# MCP1726_PINOUT.net
KiCad netlist of a schematic drawn in Altium Designer
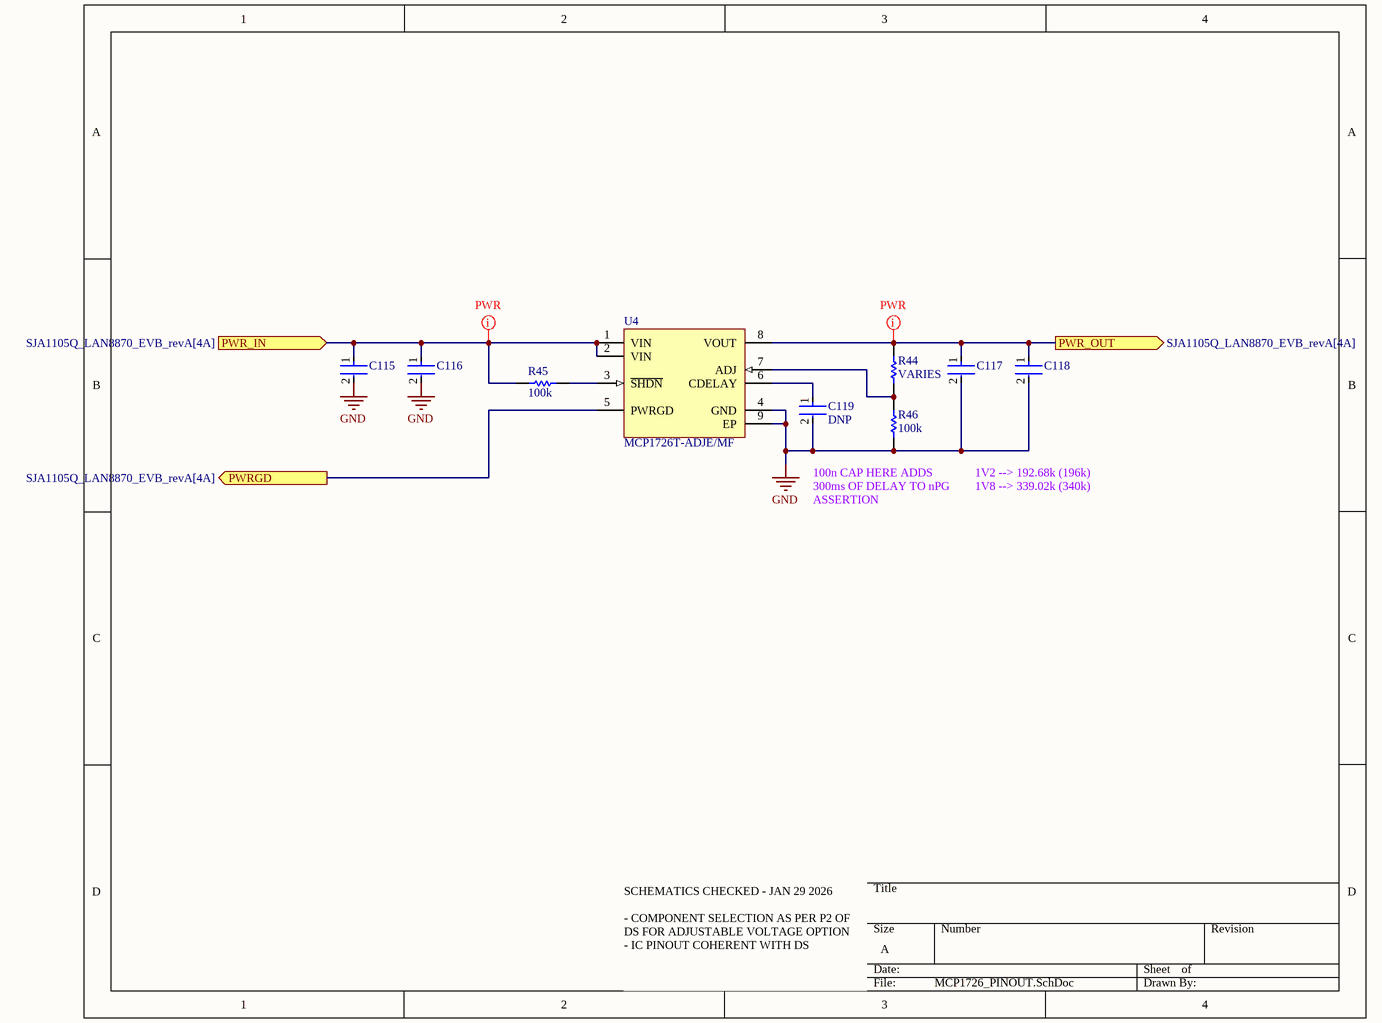
[diagram p0: MCP1726_PINOUT.SchDoc]

(export (version "E")
  (design (tool "Eeschema 10.0.6"))
  (components
    (comp (ref "C115")
      (value "C0805C475J4RACAUTO")
      (footprint "FP-C0805C475J4RACAUTO-MFG")
      (description "C0805C475J4RACAUTO Cap Ceramic 4.7uF 16V X7R 5% Pad SMD 0805 125C Automotive T/R")
      (fields (field (name "TOLERANCE") "5%"))
      (libsource (lib "Altium Content Vault") (part "b4654b650e69147ec39a6b967a45e02"))
    )
    (comp (ref "C116")
      (value "DNP")
      (footprint "FP-C0805C475J4RACAUTO-MFG")
      (description "C0805C475J4RACAUTO Cap Ceramic 4.7uF 16V X7R 5% Pad SMD 0805 125C Automotive T/R")
      (fields (field (name "TOLERANCE") "5%"))
      (libsource (lib "Altium Content Vault") (part "b4654b650e69147ec39a6b967a45e02"))
    )
    (comp (ref "C117")
      (value "HMK325B7105KN-T")
      (footprint "FP-1210-L_3_2_0_3-W_2_5_0-IPC_B")
      (description "None")
      (fields (field (name "TOLERANCE") "10%") (field (name "VOLTAGE") "100V"))
      (libsource (lib "Altium Content Vault") (part "02cd4be3c70576c341d710602a673aa"))
    )
    (comp (ref "C118")
      (value "DNP")
      (footprint "FP-1210-L_3_2_0_3-W_2_5_0-IPC_B")
      (description "None")
      (fields (field (name "TOLERANCE") "10%") (field (name "VOLTAGE") "100V"))
      (libsource (lib "Altium Content Vault") (part "02cd4be3c70576c341d710602a673aa"))
    )
    (comp (ref "C119")
      (value "DNP")
      (footprint "FP-0402-L_1_0_0_05-W_0_5-IPC_A")
      (description "LARGE PADS, 0402 CAP, CHANGE COMMENT TO MATCH REAL P/N")
      (libsource (lib "Space Concordia") (part "b4654b650e69147ec39a6b967a45e02"))
    )
    (comp (ref "R44")
      (value "VARIES")
      (footprint "R0603B")
      (description "Resistor")
      (libsource (lib "Space Concordia") (part "Resistor"))
    )
    (comp (ref "R45")
      (value "100k")
      (footprint "R0603B")
      (description "Resistor")
      (libsource (lib "Space Concordia") (part "Resistor"))
    )
    (comp (ref "R46")
      (value "100k")
      (footprint "R0603B")
      (description "Resistor")
      (libsource (lib "Space Concordia") (part "Resistor"))
    )
    (comp (ref "U4")
      (value "MCP1726T-ADJE/MF")
      (footprint "DFN-MF8")
      (libsource (lib "Altium Content Vault") (part "PM-LINEREG-MCP1726-IL9A"))
    )
  )
  (nets
    (net (code "1") (name "/PWRGD") (class "Default")
      (node (ref "U4") (pin "5") (pinfunction "PWRGD_5") (pintype "power_in"))
    )
    (net (code "2") (name "/PWR_IN") (class "Default")
      (node (ref "C115") (pin "1") (pinfunction "1_1") (pintype "passive"))
      (node (ref "C116") (pin "1") (pinfunction "1_1") (pintype "passive"))
      (node (ref "R45") (pin "1") (pinfunction "1_1") (pintype "passive"))
      (node (ref "U4") (pin "1") (pinfunction "VIN_1") (pintype "power_in"))
      (node (ref "U4") (pin "2") (pinfunction "VIN_2") (pintype "power_in"))
    )
    (net (code "3") (name "/PWR_OUT") (class "Default")
      (node (ref "C117") (pin "1") (pinfunction "1_1") (pintype "passive"))
      (node (ref "C118") (pin "1") (pinfunction "1_1") (pintype "passive"))
      (node (ref "R44") (pin "2") (pinfunction "2_2") (pintype "passive"))
      (node (ref "U4") (pin "8") (pinfunction "VOUT_8") (pintype "power_in"))
    )
    (net (code "4") (name "GND") (class "Default")
      (node (ref "C115") (pin "2") (pinfunction "2_2") (pintype "passive"))
      (node (ref "C116") (pin "2") (pinfunction "2_2") (pintype "passive"))
      (node (ref "C117") (pin "2") (pinfunction "2_2") (pintype "passive"))
      (node (ref "C118") (pin "2") (pinfunction "2_2") (pintype "passive"))
      (node (ref "C119") (pin "2") (pinfunction "2_2") (pintype "passive"))
      (node (ref "R46") (pin "1") (pinfunction "1_1") (pintype "passive"))
      (node (ref "U4") (pin "4") (pinfunction "GND_4") (pintype "power_in"))
      (node (ref "U4") (pin "9") (pinfunction "EP_9") (pintype "power_in"))
    )
    (net (code "5") (name "Net-(U4-ADJ)") (class "Default")
      (node (ref "R44") (pin "1") (pinfunction "1_1") (pintype "passive"))
      (node (ref "R46") (pin "2") (pinfunction "2_2") (pintype "passive"))
      (node (ref "U4") (pin "7") (pinfunction "ADJ_7") (pintype "input"))
    )
    (net (code "6") (name "Net-(U4-CDELAY)") (class "Default")
      (node (ref "C119") (pin "1") (pinfunction "1_1") (pintype "passive"))
      (node (ref "U4") (pin "6") (pinfunction "CDELAY_6") (pintype "passive"))
    )
    (net (code "7") (name "Net-(U4-~{SHDN})") (class "Default")
      (node (ref "R45") (pin "2") (pinfunction "2_2") (pintype "passive"))
      (node (ref "U4") (pin "3") (pinfunction "~{SHDN}_3") (pintype "input"))
    )
  )
)
